# CAN-Sheet.net
KiCad netlist of a schematic drawn in Altium Designer
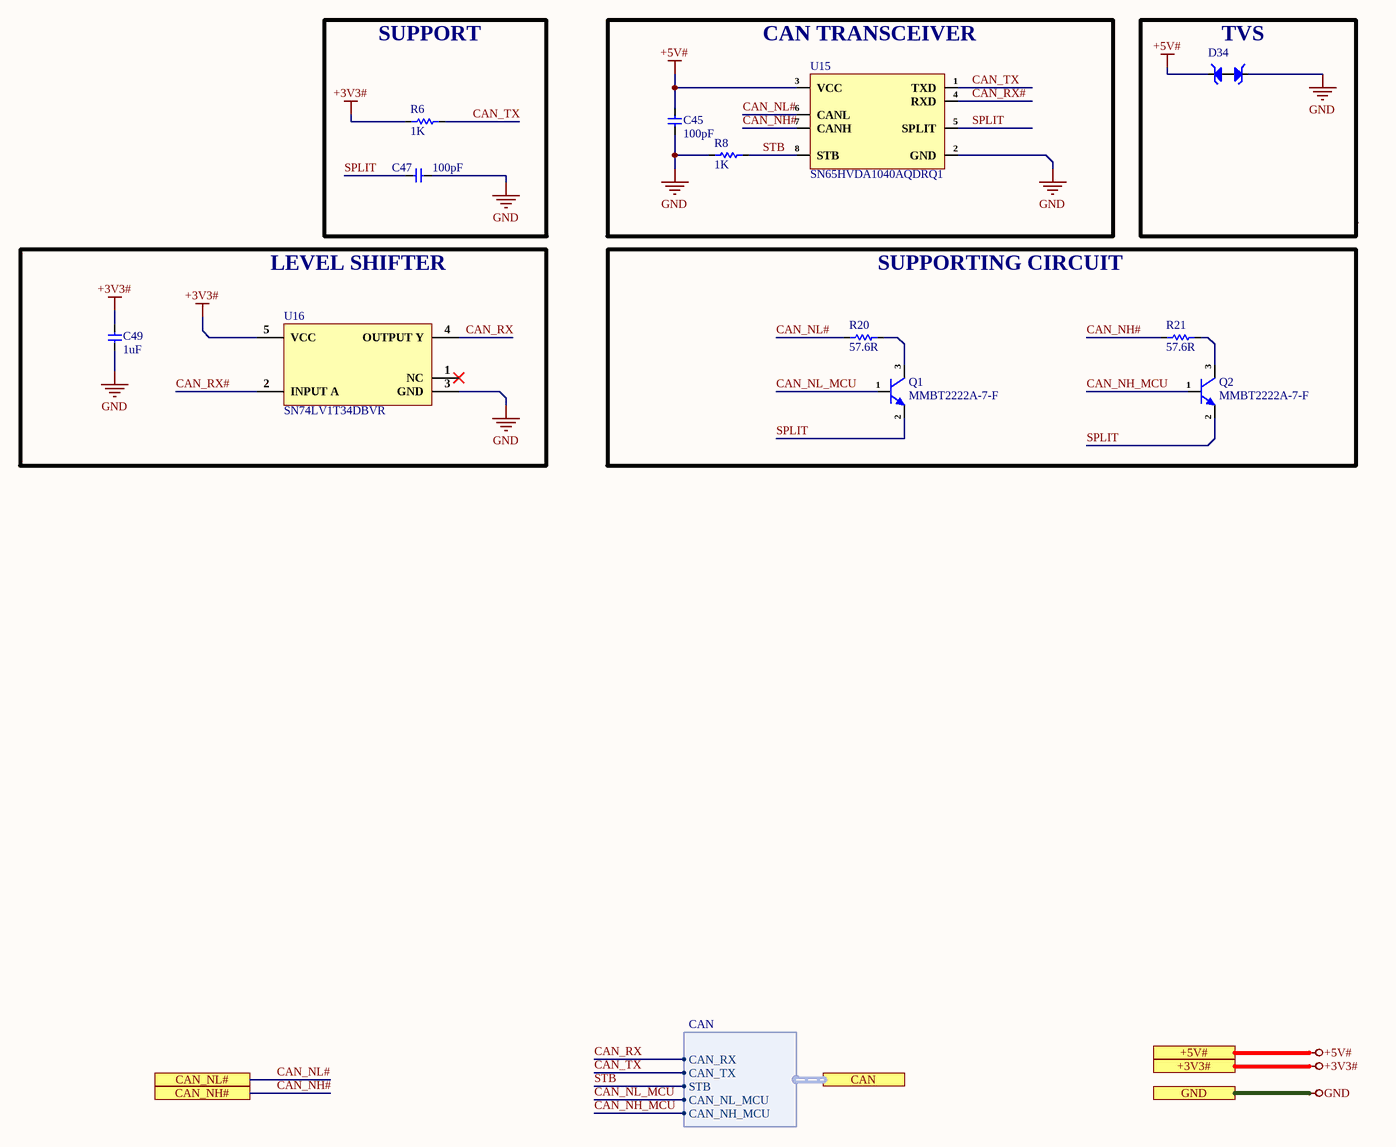
[diagram p0: CAN-Sheet.SchDoc]

(export (version "E")
  (design (tool "Eeschema 10.0.6"))
  (components
    (comp (ref "C45")
      (value "100pF")
      (footprint "Cap-0402")
      (description "CAP CER 100PF 50V C0G/NPO 0402")
      (fields
        (field (name "MANUFACTURER") "Yageo")
        (field (name "MANUFACTURER PART NUMBER") "CC0402JRNPO9BN101")
      )
      (libsource (lib "eSpark Libraries") (part "CC0402JRNPO9BN101"))
    )
    (comp (ref "C47")
      (value "100pF")
      (footprint "Cap-0402")
      (description "CAP CER 100PF 50V C0G/NPO 0402")
      (fields
        (field (name "MANUFACTURER") "Yageo")
        (field (name "MANUFACTURER PART NUMBER") "CC0402JRNPO9BN101")
      )
      (libsource (lib "eSpark Libraries") (part "CC0402JRNPO9BN101"))
    )
    (comp (ref "C49")
      (value "1uF")
      (footprint "Cap-0603")
      (description "CAP CER 1UF 25V X5R 0603")
      (fields
        (field (name "MANUFACTURER") "Yageo")
        (field (name "MANUFACTURER PART NUMBER") "CC0603KRX5R8BB105")
      )
      (libsource (lib "eSpark Libraries") (part "CC0603KRX5R8BB105"))
    )
    (comp (ref "D34")
      (value "PESD5V0H1BSFYL")
      (footprint "DSN0603-2")
      (description "TVS DIODE 5VWM 6.3VC DSN0603-2")
      (fields (field (name "MANUFACTURER") "Nexperia") (field (name "LCSC PART NUMBER") "C477989"))
      (libsource (lib "eSpark Libraries") (part "PESD5V0H1BSFYL"))
    )
    (comp (ref "Q1")
      (value "MMBT2222A-7-F")
      (footprint "SOT-23")
      (description "TRANS NPN 40V 0.6A SMD SOT23-3")
      (fields (field (name "MANUFACTURER") "Diodes") (field (name "VOLTAGE") "40V"))
      (libsource (lib "eSpark Libraries") (part "MMBT2222A-7-F"))
    )
    (comp (ref "Q2")
      (value "MMBT2222A-7-F")
      (footprint "SOT-23")
      (description "TRANS NPN 40V 0.6A SMD SOT23-3")
      (fields (field (name "MANUFACTURER") "Diodes") (field (name "VOLTAGE") "40V"))
      (libsource (lib "eSpark Libraries") (part "MMBT2222A-7-F"))
    )
    (comp (ref "R6")
      (value "1K")
      (footprint "Res-0402")
      (description "RES 1K OHM 1% 1/16W 0402")
      (fields
        (field (name "MANUFACTURER") "Yageo")
        (field (name "MANUFACTURER PART NUMBER") "RC0402FR-071KL")
      )
      (libsource (lib "eSpark Libraries") (part "RC0402FR-071KL"))
    )
    (comp (ref "R8")
      (value "1K")
      (footprint "Res-0402")
      (description "RES SMD 1K OHM 1% 1/5W 0402")
      (fields
        (field (name "MANUFACTURER") "Vishay Dale")
        (field (name "MANUFACTURER PART NUMBER") "CRCW04021K00FKEDHP")
      )
      (libsource (lib "eSpark Libraries") (part "CRCW04021K00FKEDHP"))
    )
    (comp (ref "R20")
      (value "57.6R")
      (footprint "Res-0402")
      (description "RES SMD 57.6 OHM 1% 1/10W 0402")
      (fields
        (field (name "MANUFACTURER") "Panasonic")
        (field (name "MANUFACTURER PART NUMBER") "ERJ-2RKF57R6X")
      )
      (libsource (lib "eSpark Libraries") (part "ERJ-2RKF57R6X"))
    )
    (comp (ref "R21")
      (value "57.6R")
      (footprint "Res-0402")
      (description "RES SMD 57.6 OHM 1% 1/10W 0402")
      (fields
        (field (name "MANUFACTURER") "Panasonic")
        (field (name "MANUFACTURER PART NUMBER") "ERJ-2RKF57R6X")
      )
      (libsource (lib "eSpark Libraries") (part "ERJ-2RKF57R6X"))
    )
    (comp (ref "U15")
      (value "SN65HVDA1040AQDRQ1")
      (footprint "SOIC-8(0.154\", 3.90mm Width)")
      (description "IC TRANSCEIVER HALF 1/1 8SOIC")
      (fields (field (name "LCSC PART NUMBER") "C188675") (field (name "MANUFACTURER") "Texas Instruments"))
      (libsource (lib "eSpark Libraries") (part "SN65HVDA1040AQDRQ1"))
    )
    (comp (ref "U16")
      (value "SN74LV1T34DBVR")
      (footprint "SOT-23-5")
      (description "IC BUF NON-INVERT 5.5V SOT23-5")
      (fields (field (name "MANUFACTURER") "Texas Instruments") (field (name "LCSC PART NUMBER") "C100024"))
      (libsource (lib "eSpark Libraries") (part "SN74LV1T34DBVR"))
    )
  )
  (nets
    (net (code "2") (name "+3V3#") (class "Default")
      (node (ref "C49") (pin "2") (pinfunction "2_2") (pintype "passive"))
      (node (ref "R6") (pin "1") (pinfunction "1_1") (pintype "passive"))
      (node (ref "U16") (pin "5") (pinfunction "VCC_5") (pintype "passive"))
    )
    (net (code "3") (name "+5V#") (class "Default")
      (node (ref "C45") (pin "1") (pinfunction "1_1") (pintype "passive"))
      (node (ref "D34") (pin "2") (pinfunction "2_2") (pintype "passive"))
      (node (ref "U15") (pin "3") (pinfunction "VCC_3") (pintype "passive"))
    )
    (net (code "4") (name "/CAN_NH#") (class "Default")
      (node (ref "R21") (pin "1") (pinfunction "1_1") (pintype "passive"))
      (node (ref "U15") (pin "7") (pinfunction "CANH_7") (pintype "passive"))
    )
    (net (code "5") (name "/CAN_NH_MCU") (class "Default")
      (node (ref "Q2") (pin "1") (pinfunction "B_1") (pintype "passive"))
    )
    (net (code "6") (name "/CAN_NL#") (class "Default")
      (node (ref "R20") (pin "1") (pinfunction "1_1") (pintype "passive"))
      (node (ref "U15") (pin "6") (pinfunction "CANL_6") (pintype "passive"))
    )
    (net (code "7") (name "/CAN_NL_MCU") (class "Default")
      (node (ref "Q1") (pin "1") (pinfunction "B_1") (pintype "passive"))
    )
    (net (code "8") (name "/CAN_RX") (class "Default")
      (node (ref "U16") (pin "4") (pinfunction "OUTPUT_Y_4") (pintype "passive"))
    )
    (net (code "9") (name "/CAN_RX#") (class "Default")
      (node (ref "U15") (pin "4") (pinfunction "RXD_4") (pintype "passive"))
      (node (ref "U16") (pin "2") (pinfunction "INPUT_A_2") (pintype "passive"))
    )
    (net (code "10") (name "/CAN_TX") (class "Default")
      (node (ref "R6") (pin "2") (pinfunction "2_2") (pintype "passive"))
      (node (ref "U15") (pin "1") (pinfunction "TXD_1") (pintype "passive"))
    )
    (net (code "11") (name "/SPLIT") (class "Default")
      (node (ref "C47") (pin "2") (pinfunction "2_2") (pintype "passive"))
      (node (ref "Q1") (pin "2") (pinfunction "E_2") (pintype "passive"))
      (node (ref "Q2") (pin "2") (pinfunction "E_2") (pintype "passive"))
      (node (ref "U15") (pin "5") (pinfunction "SPLIT_5") (pintype "passive"))
    )
    (net (code "12") (name "/STB") (class "Default")
      (node (ref "R8") (pin "2") (pinfunction "2_2") (pintype "passive"))
      (node (ref "U15") (pin "8") (pinfunction "STB_8") (pintype "passive"))
    )
    (net (code "14") (name "GND") (class "Default")
      (node (ref "C45") (pin "2") (pinfunction "2_2") (pintype "passive"))
      (node (ref "C47") (pin "1") (pinfunction "1_1") (pintype "passive"))
      (node (ref "C49") (pin "1") (pinfunction "1_1") (pintype "passive"))
      (node (ref "D34") (pin "1") (pinfunction "1_1") (pintype "passive"))
      (node (ref "R8") (pin "1") (pinfunction "1_1") (pintype "passive"))
      (node (ref "U15") (pin "2") (pinfunction "GND_2") (pintype "passive"))
      (node (ref "U16") (pin "3") (pinfunction "GND_3") (pintype "passive"))
    )
    (net (code "15") (name "Net-(Q1-C)") (class "Default")
      (node (ref "Q1") (pin "3") (pinfunction "C_3") (pintype "passive"))
      (node (ref "R20") (pin "2") (pinfunction "2_2") (pintype "passive"))
    )
    (net (code "16") (name "Net-(Q2-C)") (class "Default")
      (node (ref "Q2") (pin "3") (pinfunction "C_3") (pintype "passive"))
      (node (ref "R21") (pin "2") (pinfunction "2_2") (pintype "passive"))
    )
    (net (code "17") (name "unconnected-(U16-NC-Pad1)") (class "Default")
      (node (ref "U16") (pin "1") (pinfunction "NC_1") (pintype "passive+no_connect"))
    )
  )
)
